# Bitirme_deneme.net
KiCad netlist of a schematic drawn in EAGLE
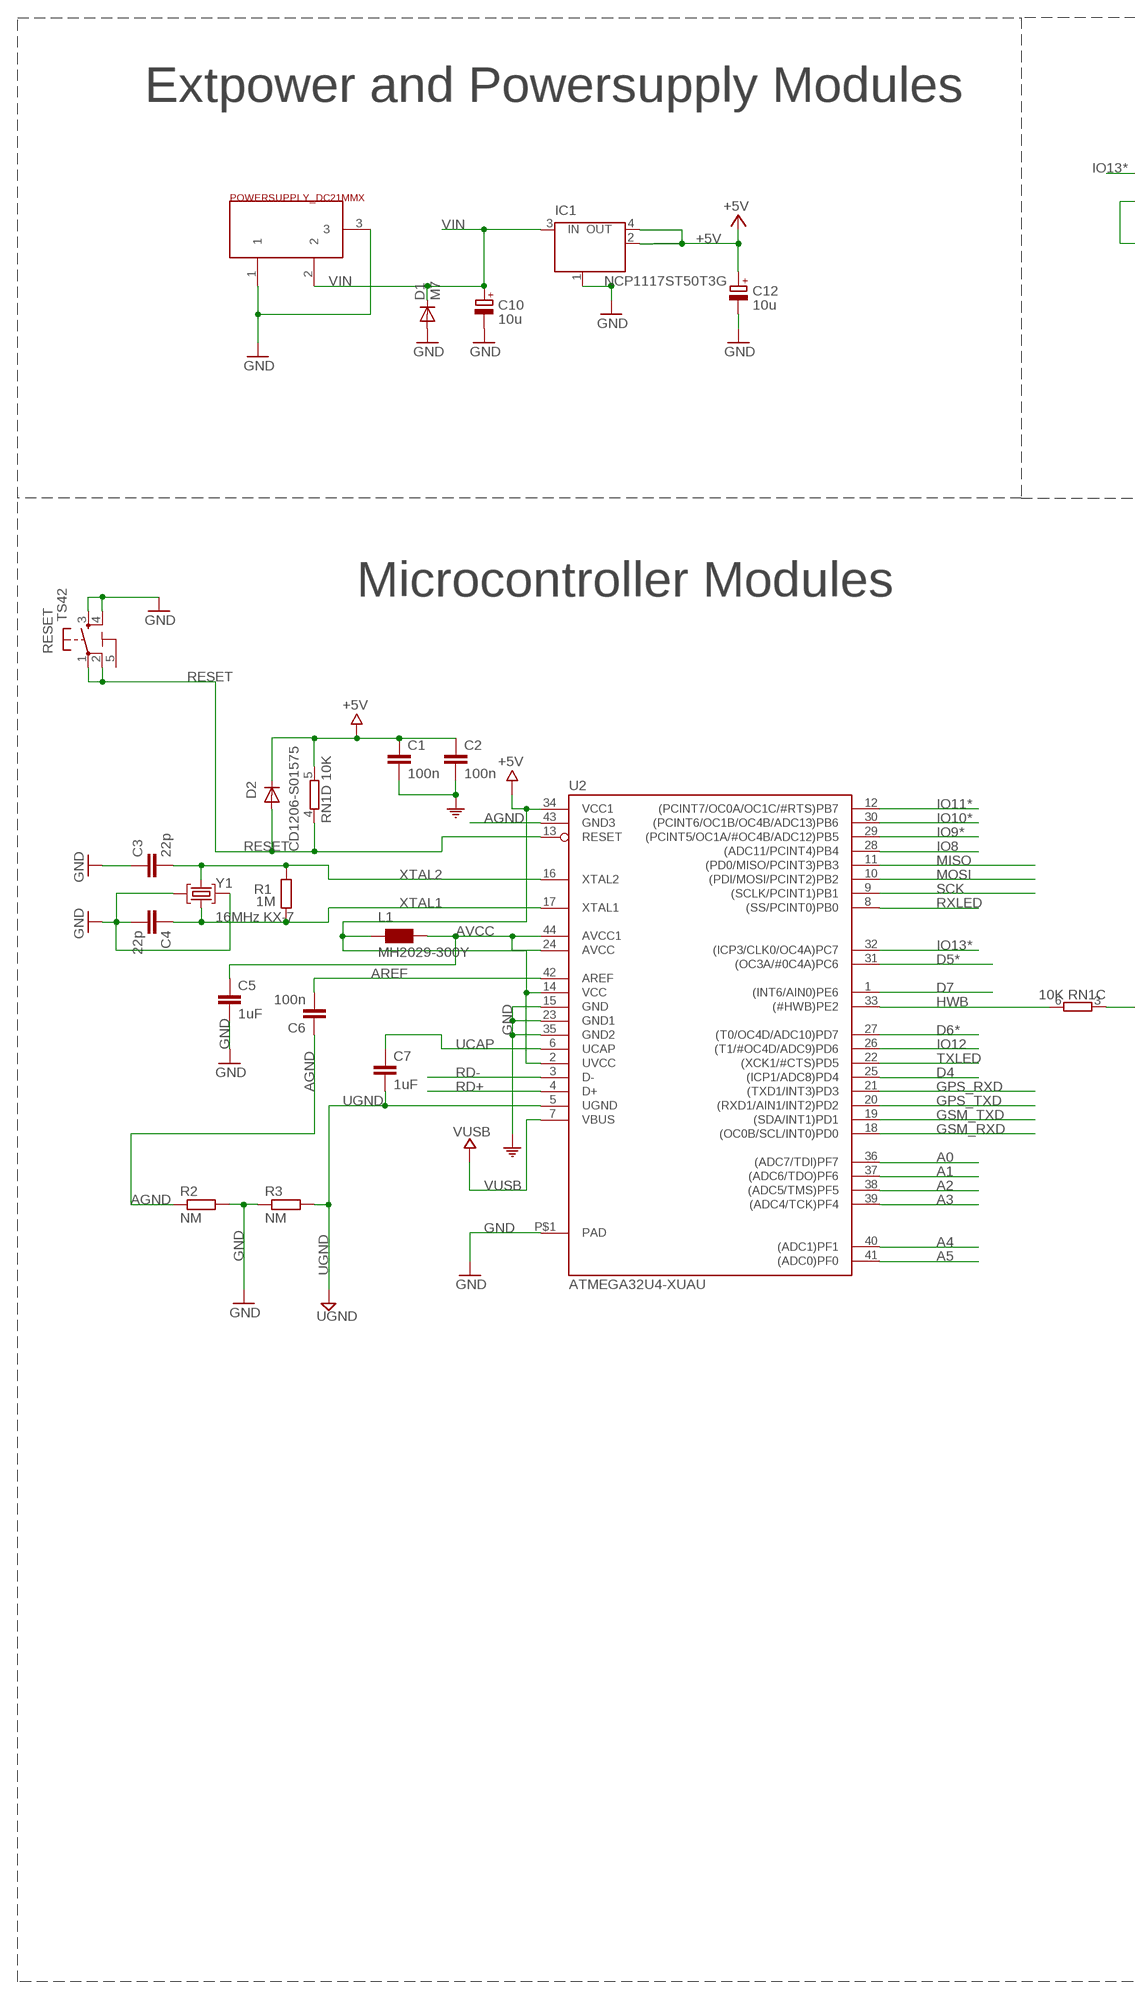
[diagram p0: schematic, sheet 1, part 1 of 2]
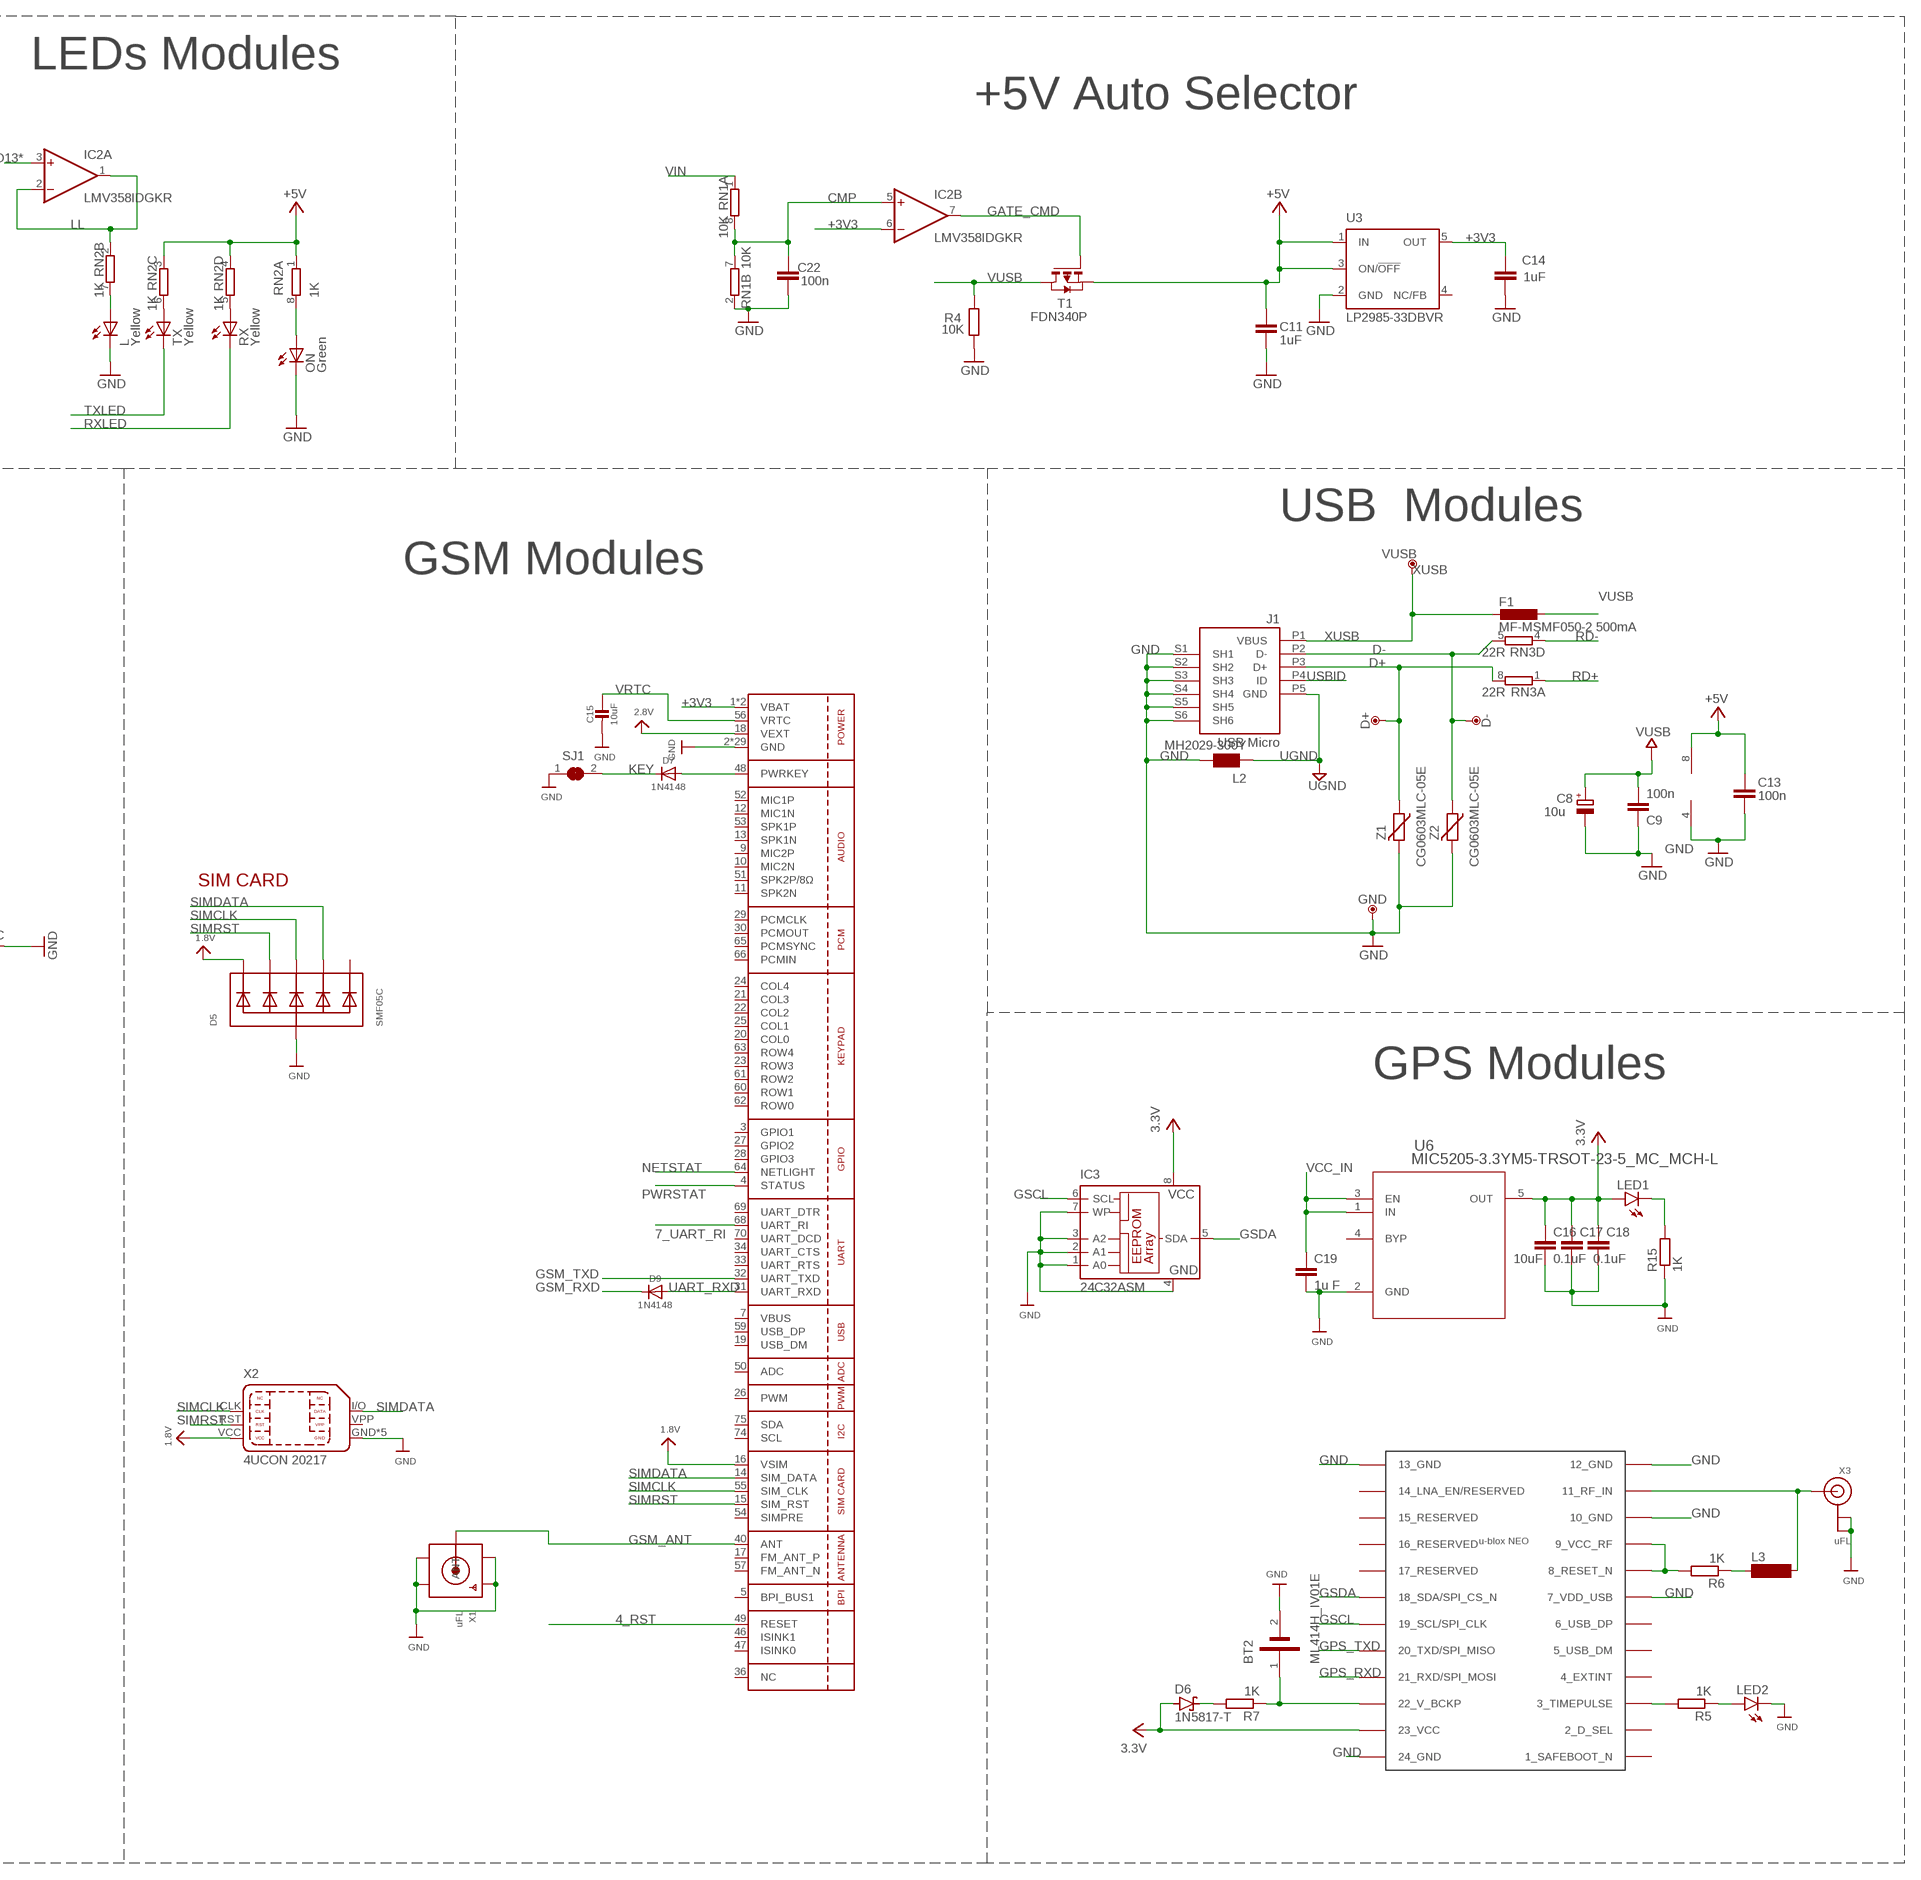
[diagram p1: schematic, sheet 1, part 2 of 2]

(export (version "E")
  (design (tool "Eeschema 10.0.6"))
  (components
    (comp (ref "BT2")
      (value "ML414H_IV01E")
      (footprint "eagle-import:SEIKO_ML414H_IV01E")
      (fields (field (name "MF") "Seiko Instruments") (field (name "MP") "ML414H IV01E"))
      (libsource (lib "eagle-import") (part "ML414H_IV01E"))
    )
    (comp (ref "C1")
      (value "100n")
      (footprint "eagle-import:C0603-ROUND")
      (libsource (lib "eagle-import") (part "C-EUC0603"))
    )
    (comp (ref "C2")
      (value "100n")
      (footprint "eagle-import:C0603-ROUND")
      (libsource (lib "eagle-import") (part "C-EUC0603"))
    )
    (comp (ref "C3")
      (value "22p")
      (footprint "eagle-import:C0603-ROUND")
      (libsource (lib "eagle-import") (part "C-EUC0603"))
    )
    (comp (ref "C4")
      (value "22p")
      (footprint "eagle-import:C0603-ROUND")
      (libsource (lib "eagle-import") (part "C-EUC0603"))
    )
    (comp (ref "C5")
      (value "1uF")
      (footprint "eagle-import:C0603-ROUND")
      (libsource (lib "eagle-import") (part "C-EUC0603"))
    )
    (comp (ref "C6")
      (value "100n")
      (footprint "eagle-import:C0603-ROUND")
      (libsource (lib "eagle-import") (part "C-EUC0603"))
    )
    (comp (ref "C7")
      (value "1uF")
      (footprint "eagle-import:C0603-ROUND")
      (libsource (lib "eagle-import") (part "C-EUC0603"))
    )
    (comp (ref "C8")
      (value "10u")
      (footprint "eagle-import:SMC_B")
      (libsource (lib "eagle-import") (part "CPOL-EUSMCB"))
    )
    (comp (ref "C9")
      (value "100n")
      (footprint "eagle-import:C0603-ROUND")
      (libsource (lib "eagle-import") (part "C-EUC0603"))
    )
    (comp (ref "C10")
      (value "10u")
      (footprint "eagle-import:SMC_B")
      (libsource (lib "eagle-import") (part "CPOL-EUSMCB"))
    )
    (comp (ref "C11")
      (value "1uF")
      (footprint "eagle-import:C0603-ROUND")
      (libsource (lib "eagle-import") (part "C-EUC0603"))
    )
    (comp (ref "C12")
      (value "10u")
      (footprint "eagle-import:SMC_B")
      (libsource (lib "eagle-import") (part "CPOL-EUSMCB"))
    )
    (comp (ref "C13")
      (value "100n")
      (footprint "eagle-import:C0603-ROUND")
      (libsource (lib "eagle-import") (part "C-EUC0603"))
    )
    (comp (ref "C14")
      (value "1uF")
      (footprint "eagle-import:C0603-ROUND")
      (libsource (lib "eagle-import") (part "C-EUC0603"))
    )
    (comp (ref "C15")
      (value "10uF")
      (footprint "eagle-import:_0805MP")
      (libsource (lib "eagle-import") (part "CAP_CERAMIC_0805MP"))
    )
    (comp (ref "C16")
      (value "10uF")
      (footprint "eagle-import:C0603K")
      (libsource (lib "eagle-import") (part "rcl_334_C-EUC0603K"))
    )
    (comp (ref "C17")
      (value "0.1uF")
      (footprint "eagle-import:C0603K")
      (libsource (lib "eagle-import") (part "rcl_334_C-EUC0603K"))
    )
    (comp (ref "C18")
      (value "0.1uF")
      (footprint "eagle-import:C0603K")
      (libsource (lib "eagle-import") (part "rcl_334_C-EUC0603K"))
    )
    (comp (ref "C19")
      (value "1u F")
      (footprint "eagle-import:C0603K")
      (libsource (lib "eagle-import") (part "rcl_334_C-EUC0603K"))
    )
    (comp (ref "C22")
      (value "100n")
      (footprint "eagle-import:C0603-ROUND")
      (libsource (lib "eagle-import") (part "C-EUC0603"))
    )
    (comp (ref "D+")
      (value "DNP")
      (footprint "eagle-import:TP-1.00MM")
      (libsource (lib "eagle-import") (part "TPTP-1.00MM"))
    )
    (comp (ref "D-")
      (value "DNP")
      (footprint "eagle-import:TP-1.00MM")
      (libsource (lib "eagle-import") (part "TPTP-1.00MM"))
    )
    (comp (ref "D1")
      (value "M7")
      (footprint "eagle-import:SMB")
      (libsource (lib "eagle-import") (part "DIODE-SMB"))
    )
    (comp (ref "D2")
      (value "CD1206-S01575")
      (footprint "eagle-import:MINIMELF")
      (libsource (lib "eagle-import") (part "DIODE-MINIMELF"))
    )
    (comp (ref "D5")
      (value "SMF05C")
      (footprint "eagle-import:SOT363")
      (libsource (lib "eagle-import") (part "TVSARRAY_5LANE"))
    )
    (comp (ref "D6")
      (value "1N5817-T")
      (footprint "eagle-import:DO41-7.6")
      (libsource (lib "eagle-import") (part "1N5817-T"))
    )
    (comp (ref "D7")
      (value "1N4148")
      (footprint "eagle-import:SOD-323")
      (libsource (lib "eagle-import") (part "DIODESOD-323"))
    )
    (comp (ref "D9")
      (value "1N4148")
      (footprint "eagle-import:SOD-323")
      (libsource (lib "eagle-import") (part "DIODESOD-323"))
    )
    (comp (ref "EXTPOWER")
      (value "POWERSUPPLY_DC21MMX")
      (footprint "eagle-import:POWERSUPPLY_DC-21MM")
      (libsource (lib "eagle-import") (part "POWERSUPPLY_DC21MMX"))
    )
    (comp (ref "F1")
      (value "MF-MSMF050-2 500mA")
      (footprint "eagle-import:L1812")
      (libsource (lib "eagle-import") (part "L-EUL1812"))
    )
    (comp (ref "GND")
      (value "DNP")
      (footprint "eagle-import:TP-1.00MM")
      (libsource (lib "eagle-import") (part "TPTP-1.00MM"))
    )
    (comp (ref "IC1")
      (value "NCP1117ST50T3G")
      (footprint "eagle-import:SOT223")
      (libsource (lib "eagle-import") (part "MC33269ST-3.3T3"))
    )
    (comp (ref "IC2")
      (value "LMV358IDGKR")
      (footprint "eagle-import:MSOP08")
      (libsource (lib "eagle-import") (part "LMV358?MMX"))
    )
    (comp (ref "IC3")
      (value "24C32ASM")
      (footprint "eagle-import:SO-08M")
      (fields (field (name "MPN") "IS24C32A-2GLI"))
      (libsource (lib "eagle-import") (part "24SMC32A"))
    )
    (comp (ref "J1")
      (value "USB Micro")
      (footprint "eagle-import:CON2_USB_MICRO_B_AT")
      (fields (field (name "MANUFACTURER") "FCI"))
      (libsource (lib "eagle-import") (part "USB-MICRO-LEGACY"))
    )
    (comp (ref "L")
      (value "Yellow")
      (footprint "eagle-import:CHIPLED_0805")
      (libsource (lib "eagle-import") (part "LEDCHIPLED_0805"))
    )
    (comp (ref "L1")
      (value "MH2029-300Y")
      (footprint "eagle-import:0805")
      (libsource (lib "eagle-import") (part "WE-CBF_0805"))
    )
    (comp (ref "L2")
      (value "MH2029-300Y")
      (footprint "eagle-import:0805")
      (libsource (lib "eagle-import") (part "WE-CBF_0805"))
    )
    (comp (ref "L3")
      (value "SM-1206")
      (footprint "eagle-import:SM-1206")
      (libsource (lib "eagle-import") (part "SM-1206"))
    )
    (comp (ref "LED1")
      (value "LEDCHIP-LED0603")
      (footprint "eagle-import:CHIP-LED0603")
      (libsource (lib "eagle-import") (part "led_259_LEDCHIP-LED0603"))
    )
    (comp (ref "LED2")
      (value "LEDCHIPLED_1206")
      (footprint "eagle-import:CHIPLED_1206")
      (libsource (lib "eagle-import") (part "led_259_LEDCHIPLED_1206"))
    )
    (comp (ref "ON")
      (value "Green")
      (footprint "eagle-import:CHIPLED_0805")
      (libsource (lib "eagle-import") (part "LEDCHIPLED_0805"))
    )
    (comp (ref "R1")
      (value "1M")
      (footprint "eagle-import:R0603-ROUND")
      (libsource (lib "eagle-import") (part "R-EU_R0603"))
    )
    (comp (ref "R2")
      (value "NM")
      (footprint "eagle-import:R0402")
      (libsource (lib "eagle-import") (part "R-EU_R0402"))
    )
    (comp (ref "R3")
      (value "NM")
      (footprint "eagle-import:R0402")
      (libsource (lib "eagle-import") (part "R-EU_R0402"))
    )
    (comp (ref "R4")
      (value "10K")
      (footprint "eagle-import:R0603-ROUND")
      (libsource (lib "eagle-import") (part "R-EU_R0603"))
    )
    (comp (ref "R5")
      (value "1K")
      (footprint "eagle-import:R0402")
      (libsource (lib "eagle-import") (part "R-EU_R0402"))
    )
    (comp (ref "R6")
      (value "1K")
      (footprint "eagle-import:R0402")
      (libsource (lib "eagle-import") (part "R-EU_R0402"))
    )
    (comp (ref "R7")
      (value "1K")
      (footprint "eagle-import:R0402")
      (libsource (lib "eagle-import") (part "R-EU_R0402"))
    )
    (comp (ref "R15")
      (value "1K")
      (footprint "eagle-import:R0402")
      (libsource (lib "eagle-import") (part "R-EU_R0402"))
    )
    (comp (ref "RESET")
      (value "TS42")
      (footprint "eagle-import:TS42")
      (libsource (lib "eagle-import") (part "TS42"))
    )
    (comp (ref "RN1")
      (value "10K")
      (footprint "eagle-import:CAY16")
      (libsource (lib "eagle-import") (part "4R-NCAY16"))
    )
    (comp (ref "RN2")
      (value "1K")
      (footprint "eagle-import:CAY16")
      (libsource (lib "eagle-import") (part "4R-NCAY16"))
    )
    (comp (ref "RN3")
      (value "22R")
      (footprint "eagle-import:CAY16")
      (libsource (lib "eagle-import") (part "4R-NCAY16"))
    )
    (comp (ref "RX")
      (value "Yellow")
      (footprint "eagle-import:CHIPLED_0805")
      (libsource (lib "eagle-import") (part "LEDCHIPLED_0805"))
    )
    (comp (ref "SJ1")
      (value "SOLDERJUMPER_CLOSED")
      (footprint "eagle-import:SOLDERJUMPER_CLOSEDWIRE")
      (libsource (lib "eagle-import") (part "SOLDERJUMPER_CLOSED"))
    )
    (comp (ref "T1")
      (value "FDN340P")
      (footprint "eagle-import:SOT-23")
      (libsource (lib "eagle-import") (part "PMOSSOT23"))
    )
    (comp (ref "TX")
      (value "Yellow")
      (footprint "eagle-import:CHIPLED_0805")
      (libsource (lib "eagle-import") (part "LEDCHIPLED_0805"))
    )
    (comp (ref "U$10")
      (value "NEO-M8")
      (footprint "eagle-import:NEO-M8")
      (libsource (lib "eagle-import") (part "NEO-M8"))
    )
    (comp (ref "U2")
      (value "ATMEGA32U4-XUAU")
      (footprint "eagle-import:TQFP44-PAD")
      (libsource (lib "eagle-import") (part "ATMEGA32U4-XUAU"))
    )
    (comp (ref "U3")
      (value "LP2985-33DBVR")
      (footprint "eagle-import:SOT23-DBV")
      (libsource (lib "eagle-import") (part "LP2985-XXDBVR33"))
    )
    (comp (ref "U4")
      (value "SIM800H/L")
      (footprint "eagle-import:SIM800L")
      (libsource (lib "eagle-import") (part "GSM_SIM800L"))
    )
    (comp (ref "U6")
      (value "MIC5205-3.3YM5-TRSOT-23-5_MC_MCH-L")
      (footprint "eagle-import:SOT-23-5_MC_MCH-L")
      (fields
        (field (name "MANUFACTURER_PART_NUMBER") "MIC5205-3.3YM5-TR")
        (field (name "COPYRIGHT") "Copyright (C) 2022 Ultra Librarian. All rights reserved.")
      )
      (libsource (lib "eagle-import") (part "MIC5205-3.3YM5-TRSOT-23-5_MC_MCH-L"))
    )
    (comp (ref "VUSB")
      (value "DNP")
      (footprint "eagle-import:TP-1.00MM")
      (libsource (lib "eagle-import") (part "TPTP-1.00MM"))
    )
    (comp (ref "X1")
      (value "uFL")
      (footprint "eagle-import:SMA_EDGELAUNCH_UFL")
      (libsource (lib "eagle-import") (part "SMACONNECTOR_EDGE_UFL"))
    )
    (comp (ref "X2")
      (value "4UCON 20217")
      (footprint "eagle-import:4UCONN_20217")
      (libsource (lib "eagle-import") (part "SIM_MICRO"))
    )
    (comp (ref "X3")
      (value "uFL")
      (footprint "eagle-import:U.FL")
      (libsource (lib "eagle-import") (part "ANTENNA_U.FL"))
    )
    (comp (ref "Y1")
      (value "16MHz KX-7")
      (footprint "eagle-import:CRYSTAL-3.2-2.5")
      (libsource (lib "eagle-import") (part "CRYSTAL-3.2-2.5"))
    )
    (comp (ref "Z1")
      (value "CG0603MLC-05E")
      (footprint "eagle-import:CT_CN0603")
      (libsource (lib "eagle-import") (part "VARISTORCN0603"))
    )
    (comp (ref "Z2")
      (value "CG0603MLC-05E")
      (footprint "eagle-import:CT_CN0603")
      (libsource (lib "eagle-import") (part "VARISTORCN0603"))
    )
  )
  (nets
    (net (code "1") (name "+5V") (class "Default")
      (node (ref "C1") (pin "1") (pinfunction "1_1") (pintype "passive"))
      (node (ref "C11") (pin "2") (pinfunction "2_2") (pintype "passive"))
      (node (ref "C12") (pin "+") (pinfunction "+_+") (pintype "passive"))
      (node (ref "C13") (pin "1") (pinfunction "1_1") (pintype "passive"))
      (node (ref "C2") (pin "1") (pinfunction "1_1") (pintype "passive"))
      (node (ref "D2") (pin "C") (pinfunction "C_C") (pintype "passive"))
      (node (ref "IC1") (pin "2") (pinfunction "OUT_2") (pintype "passive"))
      (node (ref "IC1") (pin "4") (pinfunction "OUT_4") (pintype "passive"))
      (node (ref "IC2") (pin "8") (pinfunction "V+_8") (pintype "power_in"))
      (node (ref "L1") (pin "1") (pinfunction "1_1") (pintype "passive"))
      (node (ref "RN1") (pin "5") (pinfunction "2_5") (pintype "passive"))
      (node (ref "RN2") (pin "1") (pinfunction "1_1") (pintype "passive"))
      (node (ref "RN2") (pin "3") (pinfunction "1_3") (pintype "passive"))
      (node (ref "RN2") (pin "4") (pinfunction "1_4") (pintype "passive"))
      (node (ref "T1") (pin "2") (pinfunction "S_2") (pintype "passive"))
      (node (ref "U2") (pin "14") (pinfunction "VCC_14") (pintype "power_in"))
      (node (ref "U2") (pin "2") (pinfunction "UVCC_2") (pintype "power_in"))
      (node (ref "U2") (pin "34") (pinfunction "VCC1_34") (pintype "power_in"))
      (node (ref "U3") (pin "1") (pinfunction "IN_1") (pintype "input"))
      (node (ref "U3") (pin "3") (pinfunction "ON/~{OFF}_3") (pintype "input"))
    )
    (net (code "2") (name "/+3V3") (class "Default")
      (node (ref "C14") (pin "2") (pinfunction "2_2") (pintype "passive"))
      (node (ref "IC2") (pin "6") (pinfunction "-IN_6") (pintype "input"))
      (node (ref "U3") (pin "5") (pinfunction "OUT_5") (pintype "passive"))
      (node (ref "U4") (pin "1") (pinfunction "VBAT_1") (pintype "power_in"))
      (node (ref "U4") (pin "42") (pinfunction "VBAT_42") (pintype "power_in"))
    )
    (net (code "3") (name "/4_RST") (class "Default")
      (node (ref "U4") (pin "49") (pinfunction "RESET_49") (pintype "input"))
    )
    (net (code "4") (name "/5-GND") (class "Default")
      (node (ref "RESET") (pin "5") (pinfunction "5-GND_5") (pintype "power_in"))
    )
    (net (code "5") (name "/7_UART_RI") (class "Default")
      (node (ref "U4") (pin "68") (pinfunction "UART_RI_68") (pintype "output"))
    )
    (net (code "6") (name "/A0") (class "Default")
      (node (ref "U2") (pin "36") (pinfunction "(ADC7/TDI)PF7_36") (pintype "bidirectional"))
    )
    (net (code "7") (name "/A1") (class "Default")
      (node (ref "U2") (pin "37") (pinfunction "(ADC6/TDO)PF6_37") (pintype "bidirectional"))
    )
    (net (code "8") (name "/A2") (class "Default")
      (node (ref "U2") (pin "38") (pinfunction "(ADC5/TMS)PF5_38") (pintype "bidirectional"))
    )
    (net (code "9") (name "/A3") (class "Default")
      (node (ref "U2") (pin "39") (pinfunction "(ADC4/TCK)PF4_39") (pintype "bidirectional"))
    )
    (net (code "10") (name "/A4") (class "Default")
      (node (ref "U2") (pin "40") (pinfunction "(ADC1)PF1_40") (pintype "bidirectional"))
    )
    (net (code "11") (name "/A5") (class "Default")
      (node (ref "U2") (pin "41") (pinfunction "(ADC0)PF0_41") (pintype "bidirectional"))
    )
    (net (code "12") (name "/AGND") (class "Default")
      (node (ref "C6") (pin "1") (pinfunction "1_1") (pintype "passive"))
      (node (ref "R2") (pin "1") (pinfunction "1_1") (pintype "passive"))
      (node (ref "U2") (pin "43") (pinfunction "GND3_43") (pintype "power_in"))
    )
    (net (code "13") (name "/AREF") (class "Default")
      (node (ref "C6") (pin "2") (pinfunction "2_2") (pintype "passive"))
      (node (ref "U2") (pin "42") (pinfunction "AREF_42") (pintype "power_in"))
    )
    (net (code "14") (name "/AVCC") (class "Default")
      (node (ref "C5") (pin "1") (pinfunction "1_1") (pintype "passive"))
      (node (ref "L1") (pin "2") (pinfunction "2_2") (pintype "passive"))
      (node (ref "U2") (pin "24") (pinfunction "AVCC_24") (pintype "power_in"))
      (node (ref "U2") (pin "44") (pinfunction "AVCC1_44") (pintype "power_in"))
    )
    (net (code "15") (name "/CMP") (class "Default")
      (node (ref "C22") (pin "2") (pinfunction "2_2") (pintype "passive"))
      (node (ref "IC2") (pin "5") (pinfunction "+IN_5") (pintype "input"))
      (node (ref "RN1") (pin "7") (pinfunction "2_7") (pintype "passive"))
      (node (ref "RN1") (pin "8") (pinfunction "2_8") (pintype "passive"))
    )
    (net (code "16") (name "/D+") (class "Default")
      (node (ref "D+") (pin "X") (pinfunction "P$1_X") (pintype "passive"))
      (node (ref "J1") (pin "P3") (pinfunction "D+_P3") (pintype "bidirectional"))
      (node (ref "RN3") (pin "8") (pinfunction "2_8") (pintype "passive"))
      (node (ref "Z1") (pin "1") (pinfunction "1_1") (pintype "passive"))
    )
    (net (code "17") (name "/D-") (class "Default")
      (node (ref "D-") (pin "X") (pinfunction "P$1_X") (pintype "passive"))
      (node (ref "J1") (pin "P2") (pinfunction "D-_P2") (pintype "bidirectional"))
      (node (ref "RN3") (pin "5") (pinfunction "2_5") (pintype "passive"))
      (node (ref "Z2") (pin "1") (pinfunction "1_1") (pintype "passive"))
    )
    (net (code "18") (name "/D4") (class "Default")
      (node (ref "U2") (pin "25") (pinfunction "(ICP1/ADC8)PD4_25") (pintype "bidirectional"))
    )
    (net (code "19") (name "/D5*") (class "Default")
      (node (ref "U2") (pin "31") (pinfunction "(OC3A/#0C4A)PC6_31") (pintype "bidirectional"))
    )
    (net (code "20") (name "/D6*") (class "Default")
      (node (ref "U2") (pin "27") (pinfunction "(T0/OC4D/ADC10)PD7_27") (pintype "bidirectional"))
    )
    (net (code "21") (name "/D7") (class "Default")
      (node (ref "U2") (pin "1") (pinfunction "(INT6/AIN0)PE6_1") (pintype "bidirectional"))
    )
    (net (code "22") (name "/GATE_CMD") (class "Default")
      (node (ref "IC2") (pin "7") (pinfunction "OUT_7") (pintype "output"))
      (node (ref "T1") (pin "3") (pinfunction "G_3") (pintype "passive"))
    )
    (net (code "23") (name "/GPS_RXD") (class "Default")
      (node (ref "U$10") (pin "21") (pinfunction "21_RXD/SPI_MOSI_21") (pintype "bidirectional"))
      (node (ref "U2") (pin "21") (pinfunction "(TXD1/INT3)PD3_21") (pintype "bidirectional"))
    )
    (net (code "24") (name "/GPS_TXD") (class "Default")
      (node (ref "U$10") (pin "20") (pinfunction "20_TXD/SPI_MISO_20") (pintype "bidirectional"))
      (node (ref "U2") (pin "20") (pinfunction "(RXD1/AIN1/INT2)PD2_20") (pintype "bidirectional"))
    )
    (net (code "25") (name "/GSCL") (class "Default")
      (node (ref "IC3") (pin "6") (pinfunction "SCL_6") (pintype "input"))
      (node (ref "U$10") (pin "19") (pinfunction "19_SCL/SPI_CLK_19") (pintype "bidirectional"))
    )
    (net (code "26") (name "/GSDA") (class "Default")
      (node (ref "IC3") (pin "5") (pinfunction "SDA_5") (pintype "bidirectional"))
      (node (ref "U$10") (pin "18") (pinfunction "18_SDA/SPI_CS_N_18") (pintype "bidirectional"))
    )
    (net (code "27") (name "/GSM_ANT") (class "Default")
      (node (ref "U4") (pin "40") (pinfunction "ANT_40") (pintype "bidirectional"))
      (node (ref "X1") (pin "P") (pinfunction "ANT_P") (pintype "bidirectional"))
    )
    (net (code "28") (name "/GSM_RXD") (class "Default")
      (node (ref "D9") (pin "C") (pinfunction "C_C") (pintype "passive"))
      (node (ref "U2") (pin "18") (pinfunction "(OC0B/SCL/INT0)PD0_18") (pintype "bidirectional"))
    )
    (net (code "29") (name "/GSM_TXD") (class "Default")
      (node (ref "U2") (pin "19") (pinfunction "(SDA/INT1)PD1_19") (pintype "bidirectional"))
      (node (ref "U4") (pin "32") (pinfunction "UART_TXD_32") (pintype "output"))
    )
    (net (code "30") (name "/HWB") (class "Default")
      (node (ref "RN1") (pin "6") (pinfunction "2_6") (pintype "passive"))
      (node (ref "U2") (pin "33") (pinfunction "(#HWB)PE2_33") (pintype "bidirectional"))
    )
    (net (code "31") (name "/IO8") (class "Default")
      (node (ref "U2") (pin "28") (pinfunction "(ADC11/PCINT4)PB4_28") (pintype "bidirectional"))
    )
    (net (code "32") (name "/IO9*") (class "Default")
      (node (ref "U2") (pin "29") (pinfunction "(PCINT5/OC1A/#OC4B/ADC12)PB5_29") (pintype "bidirectional"))
    )
    (net (code "33") (name "/IO10*") (class "Default")
      (node (ref "U2") (pin "30") (pinfunction "(PCINT6/OC1B/OC4B/ADC13)PB6_30") (pintype "bidirectional"))
    )
    (net (code "34") (name "/IO11*") (class "Default")
      (node (ref "U2") (pin "12") (pinfunction "(PCINT7/OC0A/OC1C/#RTS)PB7_12") (pintype "bidirectional"))
    )
    (net (code "35") (name "/IO12") (class "Default")
      (node (ref "U2") (pin "26") (pinfunction "(T1/#OC4D/ADC9)PD6_26") (pintype "bidirectional"))
    )
    (net (code "36") (name "/IO13*") (class "Default")
      (node (ref "IC2") (pin "3") (pinfunction "+IN_3") (pintype "input"))
      (node (ref "U2") (pin "32") (pinfunction "(ICP3/CLK0/OC4A)PC7_32") (pintype "bidirectional"))
    )
    (net (code "37") (name "/KEY") (class "Default")
      (node (ref "D7") (pin "C") (pinfunction "C_C") (pintype "passive"))
      (node (ref "SJ1") (pin "2") (pinfunction "2_2") (pintype "passive"))
    )
    (net (code "38") (name "/LL") (class "Default")
      (node (ref "IC2") (pin "1") (pinfunction "OUT_1") (pintype "output"))
      (node (ref "IC2") (pin "2") (pinfunction "-IN_2") (pintype "input"))
      (node (ref "RN2") (pin "2") (pinfunction "1_2") (pintype "passive"))
    )
    (net (code "39") (name "/MISO") (class "Default")
      (node (ref "U2") (pin "11") (pinfunction "(PD0/MISO/PCINT3)PB3_11") (pintype "bidirectional"))
    )
    (net (code "40") (name "/MOSI") (class "Default")
      (node (ref "U2") (pin "10") (pinfunction "(PDI/MOSI/PCINT2)PB2_10") (pintype "bidirectional"))
    )
    (net (code "41") (name "/NETSTAT") (class "Default")
      (node (ref "U4") (pin "64") (pinfunction "NETLIGHT_64") (pintype "output"))
    )
    (net (code "42") (name "/PWRSTAT") (class "Default")
      (node (ref "U4") (pin "4") (pinfunction "STATUS_4") (pintype "output"))
    )
    (net (code "43") (name "/RD+") (class "Default")
      (node (ref "RN3") (pin "1") (pinfunction "1_1") (pintype "passive"))
      (node (ref "U2") (pin "4") (pinfunction "D+_4") (pintype "bidirectional"))
    )
    (net (code "44") (name "/RD-") (class "Default")
      (node (ref "RN3") (pin "4") (pinfunction "1_4") (pintype "passive"))
      (node (ref "U2") (pin "3") (pinfunction "D-_3") (pintype "bidirectional"))
    )
    (net (code "45") (name "/RESET") (class "Default")
      (node (ref "D2") (pin "A") (pinfunction "A_A") (pintype "passive"))
      (node (ref "RESET") (pin "1") (pinfunction "1_1") (pintype "passive"))
      (node (ref "RESET") (pin "2") (pinfunction "2_2") (pintype "passive"))
      (node (ref "RN1") (pin "4") (pinfunction "1_4") (pintype "passive"))
      (node (ref "U2") (pin "13") (pinfunction "RESET_13") (pintype "input"))
    )
    (net (code "46") (name "/RXLED") (class "Default")
      (node (ref "RX") (pin "C") (pinfunction "C_C") (pintype "passive"))
      (node (ref "U2") (pin "8") (pinfunction "(SS/PCINT0)PB0_8") (pintype "bidirectional"))
    )
    (net (code "47") (name "/SCK") (class "Default")
      (node (ref "U2") (pin "9") (pinfunction "(SCLK/PCINT1)PB1_9") (pintype "bidirectional"))
    )
    (net (code "48") (name "/SIMCLK") (class "Default")
      (node (ref "D5") (pin "4") (pinfunction "C3_4") (pintype "passive"))
      (node (ref "U4") (pin "55") (pinfunction "SIM_CLK_55") (pintype "output"))
      (node (ref "X2") (pin "CLK") (pinfunction "CLK_CLK") (pintype "passive"))
    )
    (net (code "49") (name "/SIMDATA") (class "Default")
      (node (ref "D5") (pin "5") (pinfunction "C4_5") (pintype "passive"))
      (node (ref "U4") (pin "14") (pinfunction "SIM_DATA_14") (pintype "bidirectional"))
      (node (ref "X2") (pin "I/O") (pinfunction "DATA_I/O") (pintype "passive"))
    )
    (net (code "50") (name "/SIMRST") (class "Default")
      (node (ref "D5") (pin "3") (pinfunction "C2_3") (pintype "passive"))
      (node (ref "U4") (pin "15") (pinfunction "SIM_RST_15") (pintype "output"))
      (node (ref "X2") (pin "RST") (pinfunction "RST_RST") (pintype "passive"))
    )
    (net (code "51") (name "/TXLED") (class "Default")
      (node (ref "TX") (pin "C") (pinfunction "C_C") (pintype "passive"))
      (node (ref "U2") (pin "22") (pinfunction "(XCK1/#CTS)PD5_22") (pintype "bidirectional"))
    )
    (net (code "52") (name "/UART_RXD") (class "Default")
      (node (ref "D9") (pin "A") (pinfunction "A_A") (pintype "passive"))
      (node (ref "U4") (pin "31") (pinfunction "UART_RXD_31") (pintype "input"))
    )
    (net (code "53") (name "/UCAP") (class "Default")
      (node (ref "C7") (pin "1") (pinfunction "1_1") (pintype "passive"))
      (node (ref "U2") (pin "6") (pinfunction "UCAP_6") (pintype "passive"))
    )
    (net (code "54") (name "/USBID") (class "Default")
      (node (ref "J1") (pin "P4") (pinfunction "ID_P4") (pintype "bidirectional"))
    )
    (net (code "55") (name "/VBUS") (class "Default")
      (node (ref "U4") (pin "7") (pinfunction "VBUS_7") (pintype "power_in"))
    )
    (net (code "56") (name "/VCC_IN") (class "Default")
      (node (ref "C19") (pin "1") (pinfunction "1_1") (pintype "passive"))
      (node (ref "U6") (pin "1") (pinfunction "IN_1") (pintype "input"))
      (node (ref "U6") (pin "3") (pinfunction "EN_3") (pintype "input"))
    )
    (net (code "57") (name "/VIN") (class "Default")
      (node (ref "C10") (pin "+") (pinfunction "+_+") (pintype "passive"))
      (node (ref "D1") (pin "C") (pinfunction "C_C") (pintype "passive"))
      (node (ref "EXTPOWER") (pin "2") (pinfunction "2_2") (pintype "power_in"))
      (node (ref "IC1") (pin "3") (pinfunction "IN_3") (pintype "input"))
      (node (ref "RN1") (pin "1") (pinfunction "1_1") (pintype "passive"))
    )
    (net (code "58") (name "/VRTC") (class "Default")
      (node (ref "C15") (pin "1") (pinfunction "1_1") (pintype "passive"))
      (node (ref "U4") (pin "56") (pinfunction "VRTC_56") (pintype "power_in"))
    )
    (net (code "59") (name "/XTAL1") (class "Default")
      (node (ref "C4") (pin "1") (pinfunction "1_1") (pintype "passive"))
      (node (ref "R1") (pin "1") (pinfunction "1_1") (pintype "passive"))
      (node (ref "U2") (pin "17") (pinfunction "XTAL1_17") (pintype "bidirectional"))
      (node (ref "Y1") (pin "1") (pinfunction "C1_1") (pintype "passive"))
    )
    (net (code "60") (name "/XTAL2") (class "Default")
      (node (ref "C3") (pin "2") (pinfunction "2_2") (pintype "passive"))
      (node (ref "R1") (pin "2") (pinfunction "2_2") (pintype "passive"))
      (node (ref "U2") (pin "16") (pinfunction "XTAL2_16") (pintype "bidirectional"))
      (node (ref "Y1") (pin "3") (pinfunction "C2_3") (pintype "passive"))
    )
    (net (code "61") (name "/XUSB") (class "Default")
      (node (ref "F1") (pin "2") (pinfunction "2_2") (pintype "passive"))
      (node (ref "J1") (pin "P1") (pinfunction "VBUS_P1") (pintype "power_in"))
      (node (ref "VUSB") (pin "X") (pinfunction "P$1_X") (pintype "passive"))
    )
    (net (code "62") (name "1.8V") (class "Default")
      (node (ref "D5") (pin "1") (pinfunction "C1_1") (pintype "passive"))
      (node (ref "U4") (pin "16") (pinfunction "VSIM_16") (pintype "power_in"))
      (node (ref "X2") (pin "VCC") (pinfunction "VCC_VCC") (pintype "passive"))
    )
    (net (code "63") (name "2.8V") (class "Default")
      (node (ref "U4") (pin "18") (pinfunction "VEXT_18") (pintype "power_in"))
    )
    (net (code "64") (name "3.3V") (class "Default")
      (node (ref "C16") (pin "1") (pinfunction "1_1") (pintype "passive"))
      (node (ref "C17") (pin "1") (pinfunction "1_1") (pintype "passive"))
      (node (ref "C18") (pin "1") (pinfunction "1_1") (pintype "passive"))
      (node (ref "D6") (pin "A") (pinfunction "A_A") (pintype "passive"))
      (node (ref "IC3") (pin "8") (pinfunction "VCC_8") (pintype "power_in"))
      (node (ref "LED1") (pin "A") (pinfunction "A_A") (pintype "passive"))
      (node (ref "U$10") (pin "23") (pinfunction "23_VCC_23") (pintype "bidirectional"))
      (node (ref "U6") (pin "5") (pinfunction "OUT_5") (pintype "output"))
    )
    (net (code "65") (name "COM") (class "Default")
      (node (ref "BT2") (pin "2") (pinfunction "NEG_2") (pintype "passive"))
      (node (ref "C1") (pin "2") (pinfunction "2_2") (pintype "passive"))
      (node (ref "C10") (pin "-") (pinfunction "-_-") (pintype "passive"))
      (node (ref "C11") (pin "1") (pinfunction "1_1") (pintype "passive"))
      (node (ref "C12") (pin "-") (pinfunction "-_-") (pintype "passive"))
      (node (ref "C13") (pin "2") (pinfunction "2_2") (pintype "passive"))
      (node (ref "C14") (pin "1") (pinfunction "1_1") (pintype "passive"))
      (node (ref "C15") (pin "2") (pinfunction "2_2") (pintype "passive"))
      (node (ref "C16") (pin "2") (pinfunction "2_2") (pintype "passive"))
      (node (ref "C17") (pin "2") (pinfunction "2_2") (pintype "passive"))
      (node (ref "C18") (pin "2") (pinfunction "2_2") (pintype "passive"))
      (node (ref "C19") (pin "2") (pinfunction "2_2") (pintype "passive"))
      (node (ref "C2") (pin "2") (pinfunction "2_2") (pintype "passive"))
      (node (ref "C22") (pin "1") (pinfunction "1_1") (pintype "passive"))
      (node (ref "C3") (pin "1") (pinfunction "1_1") (pintype "passive"))
      (node (ref "C4") (pin "2") (pinfunction "2_2") (pintype "passive"))
      (node (ref "C5") (pin "2") (pinfunction "2_2") (pintype "passive"))
      (node (ref "C8") (pin "-") (pinfunction "-_-") (pintype "passive"))
      (node (ref "C9") (pin "1") (pinfunction "1_1") (pintype "passive"))
      (node (ref "D1") (pin "A") (pinfunction "A_A") (pintype "passive"))
      (node (ref "D5") (pin "2") (pinfunction "A_2") (pintype "passive"))
      (node (ref "EXTPOWER") (pin "1") (pinfunction "1_1") (pintype "power_in"))
      (node (ref "EXTPOWER") (pin "3") (pinfunction "3_3") (pintype "power_in"))
      (node (ref "GND") (pin "X") (pinfunction "P$1_X") (pintype "passive"))
      (node (ref "IC1") (pin "1") (pinfunction "GND/ADJ_1") (pintype "input"))
      (node (ref "IC2") (pin "4") (pinfunction "V-_4") (pintype "power_in"))
      (node (ref "IC3") (pin "1") (pinfunction "A0_1") (pintype "input"))
      (node (ref "IC3") (pin "2") (pinfunction "A1_2") (pintype "input"))
      (node (ref "IC3") (pin "3") (pinfunction "A2_3") (pintype "input"))
      (node (ref "IC3") (pin "4") (pinfunction "GND_4") (pintype "power_in"))
      (node (ref "IC3") (pin "7") (pinfunction "WP_7") (pintype "input"))
      (node (ref "J1") (pin "S1") (pinfunction "SH1_S1") (pintype "passive"))
      (node (ref "J1") (pin "S2") (pinfunction "SH2_S2") (pintype "passive"))
      (node (ref "J1") (pin "S3") (pinfunction "SH3_S3") (pintype "passive"))
      (node (ref "J1") (pin "S4") (pinfunction "SH4_S4") (pintype "passive"))
      (node (ref "J1") (pin "S5") (pinfunction "SH5_S5") (pintype "passive"))
      (node (ref "J1") (pin "S6") (pinfunction "SH6_S6") (pintype "passive"))
      (node (ref "L") (pin "C") (pinfunction "C_C") (pintype "passive"))
      (node (ref "L2") (pin "2") (pinfunction "2_2") (pintype "passive"))
      (node (ref "LED2") (pin "C") (pinfunction "C_C") (pintype "passive"))
      (node (ref "ON") (pin "C") (pinfunction "C_C") (pintype "passive"))
      (node (ref "R15") (pin "1") (pinfunction "1_1") (pintype "passive"))
      (node (ref "R2") (pin "2") (pinfunction "2_2") (pintype "passive"))
      (node (ref "R3") (pin "1") (pinfunction "1_1") (pintype "passive"))
      (node (ref "R4") (pin "1") (pinfunction "1_1") (pintype "passive"))
      (node (ref "RESET") (pin "3") (pinfunction "3_3") (pintype "passive"))
      (node (ref "RESET") (pin "4") (pinfunction "4_4") (pintype "passive"))
      (node (ref "RN1") (pin "2") (pinfunction "1_2") (pintype "passive"))
      (node (ref "RN1") (pin "3") (pinfunction "1_3") (pintype "passive"))
      (node (ref "SJ1") (pin "1") (pinfunction "1_1") (pintype "passive"))
      (node (ref "U$10") (pin "10") (pinfunction "10_GND_10") (pintype "bidirectional"))
      (node (ref "U$10") (pin "12") (pinfunction "12_GND_12") (pintype "bidirectional"))
      (node (ref "U$10") (pin "13") (pinfunction "13_GND_13") (pintype "bidirectional"))
      (node (ref "U$10") (pin "24") (pinfunction "24_GND_24") (pintype "bidirectional"))
      (node (ref "U$10") (pin "7") (pinfunction "7_VDD_USB_7") (pintype "bidirectional"))
      (node (ref "U2") (pin "15") (pinfunction "GND_15") (pintype "power_in"))
      (node (ref "U2") (pin "23") (pinfunction "GND1_23") (pintype "power_in"))
      (node (ref "U2") (pin "35") (pinfunction "GND2_35") (pintype "power_in"))
      (node (ref "U2") (pin "P$1") (pinfunction "PAD_P$1") (pintype "power_in"))
      (node (ref "U3") (pin "2") (pinfunction "GND_2") (pintype "power_in"))
      (node (ref "U4") (pin "2") (pinfunction "GND_2") (pintype "power_in"))
      (node (ref "U4") (pin "35") (pinfunction "GND_35") (pintype "power_in"))
      (node (ref "U4") (pin "37") (pinfunction "GND_37") (pintype "power_in"))
      (node (ref "U4") (pin "38") (pinfunction "GND_38") (pintype "power_in"))
      (node (ref "U4") (pin "39") (pinfunction "GND_39") (pintype "power_in"))
      (node (ref "U4") (pin "41") (pinfunction "GND_41") (pintype "power_in"))
      (node (ref "U4") (pin "43") (pinfunction "GND_43") (pintype "power_in"))
      (node (ref "U4") (pin "44") (pinfunction "GND_44") (pintype "power_in"))
      (node (ref "U4") (pin "45") (pinfunction "GND_45") (pintype "power_in"))
      (node (ref "U4") (pin "58") (pinfunction "GND_58") (pintype "power_in"))
      (node (ref "U4") (pin "6") (pinfunction "GND_6") (pintype "power_in"))
      (node (ref "U4") (pin "67") (pinfunction "GND_67") (pintype "power_in"))
      (node (ref "U4") (pin "71") (pinfunction "GND_71") (pintype "power_in"))
      (node (ref "U4") (pin "72") (pinfunction "GND_72") (pintype "power_in"))
      (node (ref "U4") (pin "73") (pinfunction "GND_73") (pintype "power_in"))
      (node (ref "U4") (pin "76") (pinfunction "GND_76") (pintype "power_in"))
      (node (ref "U4") (pin "77") (pinfunction "GND_77") (pintype "power_in"))
      (node (ref "U4") (pin "78") (pinfunction "GND_78") (pintype "power_in"))
      (node (ref "U4") (pin "79") (pinfunction "GND_79") (pintype "power_in"))
      (node (ref "U4") (pin "8") (pinfunction "GND_8") (pintype "power_in"))
      (node (ref "U4") (pin "80") (pinfunction "GND_80") (pintype "power_in"))
      (node (ref "U4") (pin "81") (pinfunction "GND_81") (pintype "power_in"))
      (node (ref "U4") (pin "82") (pinfunction "GND_82") (pintype "power_in"))
      (node (ref "U4") (pin "83") (pinfunction "GND_83") (pintype "power_in"))
      (node (ref "U4") (pin "84") (pinfunction "GND_84") (pintype "power_in"))
      (node (ref "U4") (pin "85") (pinfunction "GND_85") (pintype "power_in"))
      (node (ref "U4") (pin "86") (pinfunction "GND_86") (pintype "power_in"))
      (node (ref "U4") (pin "87") (pinfunction "GND_87") (pintype "power_in"))
      (node (ref "U4") (pin "88") (pinfunction "GND_88") (pintype "power_in"))
      (node (ref "U6") (pin "2") (pinfunction "GND_2") (pintype "power_in"))
      (node (ref "X1") (pin "GND@1") (pinfunction "GND1_GND@1") (pintype "power_in"))
      (node (ref "X1") (pin "GND@2") (pinfunction "GND2_GND@2") (pintype "power_in"))
      (node (ref "X1") (pin "GND@3") (pinfunction "GND3_GND@3") (pintype "power_in"))
      (node (ref "X1") (pin "GND@4") (pinfunction "GND4_GND@4") (pintype "power_in"))
      (node (ref "X2") (pin "GND") (pinfunction "GND_GND") (pintype "passive"))
      (node (ref "X2") (pin "GND@1") (pinfunction "GND_GND@1") (pintype "passive"))
      (node (ref "X2") (pin "GND@2") (pinfunction "GND_GND@2") (pintype "passive"))
      (node (ref "X2") (pin "GND@3") (pinfunction "GND_GND@3") (pintype "passive"))
      (node (ref "X2") (pin "GND@4") (pinfunction "GND_GND@4") (pintype "passive"))
      (node (ref "X3") (pin "1") (pinfunction "GND_1") (pintype "passive"))
      (node (ref "X3") (pin "2") (pinfunction "GND_2") (pintype "passive"))
      (node (ref "Y1") (pin "2") (pinfunction "GND_2") (pintype "passive"))
      (node (ref "Y1") (pin "4") (pinfunction "GND_4") (pintype "passive"))
      (node (ref "Z1") (pin "2") (pinfunction "2_2") (pintype "passive"))
      (node (ref "Z2") (pin "2") (pinfunction "2_2") (pintype "passive"))
    )
    (net (code "66") (name "Net-(BT2-POS)") (class "Default")
      (node (ref "BT2") (pin "1") (pinfunction "POS_1") (pintype "passive"))
      (node (ref "R7") (pin "1") (pinfunction "1_1") (pintype "passive"))
      (node (ref "U$10") (pin "22") (pinfunction "22_V_BCKP_22") (pintype "bidirectional"))
    )
    (net (code "67") (name "Net-(D6-PadC)") (class "Default")
      (node (ref "D6") (pin "C") (pinfunction "C_C") (pintype "passive"))
      (node (ref "R7") (pin "2") (pinfunction "2_2") (pintype "passive"))
    )
    (net (code "68") (name "Net-(L3-Pad1)") (class "Default")
      (node (ref "L3") (pin "1") (pinfunction "1_1") (pintype "passive"))
      (node (ref "R6") (pin "1") (pinfunction "1_1") (pintype "passive"))
    )
    (net (code "69") (name "Net-(LED1-PadC)") (class "Default")
      (node (ref "LED1") (pin "C") (pinfunction "C_C") (pintype "passive"))
      (node (ref "R15") (pin "2") (pinfunction "2_2") (pintype "passive"))
    )
    (net (code "70") (name "Net-(LED2-PadA)") (class "Default")
      (node (ref "LED2") (pin "A") (pinfunction "A_A") (pintype "passive"))
      (node (ref "R5") (pin "1") (pinfunction "1_1") (pintype "passive"))
    )
    (net (code "71") (name "Net-(RN2A-2)") (class "Default")
      (node (ref "ON") (pin "A") (pinfunction "A_A") (pintype "passive"))
      (node (ref "RN2") (pin "8") (pinfunction "2_8") (pintype "passive"))
    )
    (net (code "72") (name "Net-(RN2B-2)") (class "Default")
      (node (ref "L") (pin "A") (pinfunction "A_A") (pintype "passive"))
      (node (ref "RN2") (pin "7") (pinfunction "2_7") (pintype "passive"))
    )
    (net (code "73") (name "Net-(RN2C-2)") (class "Default")
      (node (ref "RN2") (pin "6") (pinfunction "2_6") (pintype "passive"))
      (node (ref "TX") (pin "A") (pinfunction "A_A") (pintype "passive"))
    )
    (net (code "74") (name "Net-(RN2D-2)") (class "Default")
      (node (ref "RN2") (pin "5") (pinfunction "2_5") (pintype "passive"))
      (node (ref "RX") (pin "A") (pinfunction "A_A") (pintype "passive"))
    )
    (net (code "75") (name "Net-(U$10-3_TIMEPULSE)") (class "Default")
      (node (ref "R5") (pin "2") (pinfunction "2_2") (pintype "passive"))
      (node (ref "U$10") (pin "3") (pinfunction "3_TIMEPULSE_3") (pintype "bidirectional"))
    )
    (net (code "76") (name "Net-(U$10-8_RESET_N)") (class "Default")
      (node (ref "R6") (pin "2") (pinfunction "2_2") (pintype "passive"))
      (node (ref "U$10") (pin "8") (pinfunction "8_RESET_N_8") (pintype "bidirectional"))
      (node (ref "U$10") (pin "9") (pinfunction "9_VCC_RF_9") (pintype "bidirectional"))
    )
    (net (code "77") (name "Net-(U$10-11_RF_IN)") (class "Default")
      (node (ref "L3") (pin "2") (pinfunction "2_2") (pintype "passive"))
      (node (ref "U$10") (pin "11") (pinfunction "11_RF_IN_11") (pintype "bidirectional"))
      (node (ref "X3") (pin "3") (pinfunction "SIGNAL_3") (pintype "passive"))
    )
    (net (code "78") (name "Net-(U4-PWRKEY)") (class "Default")
      (node (ref "D7") (pin "A") (pinfunction "A_A") (pintype "passive"))
      (node (ref "U4") (pin "48") (pinfunction "PWRKEY_48") (pintype "input"))
    )
    (net (code "79") (name "UGND") (class "Default")
      (node (ref "C7") (pin "2") (pinfunction "2_2") (pintype "passive"))
      (node (ref "J1") (pin "P5") (pinfunction "GND_P5") (pintype "passive"))
      (node (ref "L2") (pin "1") (pinfunction "1_1") (pintype "passive"))
      (node (ref "R3") (pin "2") (pinfunction "2_2") (pintype "passive"))
      (node (ref "U2") (pin "5") (pinfunction "UGND_5") (pintype "power_in"))
    )
    (net (code "80") (name "VUSB") (class "Default")
      (node (ref "C8") (pin "+") (pinfunction "+_+") (pintype "passive"))
      (node (ref "C9") (pin "2") (pinfunction "2_2") (pintype "passive"))
      (node (ref "F1") (pin "1") (pinfunction "1_1") (pintype "passive"))
      (node (ref "R4") (pin "2") (pinfunction "2_2") (pintype "passive"))
      (node (ref "T1") (pin "1") (pinfunction "D_1") (pintype "passive"))
      (node (ref "U2") (pin "7") (pinfunction "VBUS_7") (pintype "input"))
    )
    (net (code "81") (name "unconnected-(D5-C5-Pad6)") (class "Default")
      (node (ref "D5") (pin "6") (pinfunction "C5_6") (pintype "passive"))
    )
    (net (code "82") (name "unconnected-(U$10-1_SAFEBOOT_N-Pad1)") (class "Default")
      (node (ref "U$10") (pin "1") (pinfunction "1_SAFEBOOT_N_1") (pintype "bidirectional"))
    )
    (net (code "83") (name "unconnected-(U$10-2_D_SEL-Pad2)") (class "Default")
      (node (ref "U$10") (pin "2") (pinfunction "2_D_SEL_2") (pintype "bidirectional"))
    )
    (net (code "84") (name "unconnected-(U$10-4_EXTINT-Pad4)") (class "Default")
      (node (ref "U$10") (pin "4") (pinfunction "4_EXTINT_4") (pintype "bidirectional"))
    )
    (net (code "85") (name "unconnected-(U$10-5_USB_DM-Pad5)") (class "Default")
      (node (ref "U$10") (pin "5") (pinfunction "5_USB_DM_5") (pintype "bidirectional"))
    )
    (net (code "86") (name "unconnected-(U$10-6_USB_DP-Pad6)") (class "Default")
      (node (ref "U$10") (pin "6") (pinfunction "6_USB_DP_6") (pintype "bidirectional"))
    )
    (net (code "87") (name "unconnected-(U$10-14_LNA_EN{slash}RESERVED-Pad14)") (class "Default")
      (node (ref "U$10") (pin "14") (pinfunction "14_LNA_EN/RESERVED_14") (pintype "bidirectional"))
    )
    (net (code "88") (name "unconnected-(U$10-15_RESERVED-Pad15)") (class "Default")
      (node (ref "U$10") (pin "15") (pinfunction "15_RESERVED_15") (pintype "bidirectional"))
    )
    (net (code "89") (name "unconnected-(U$10-16_RESERVED-Pad16)") (class "Default")
      (node (ref "U$10") (pin "16") (pinfunction "16_RESERVED_16") (pintype "bidirectional"))
    )
    (net (code "90") (name "unconnected-(U$10-17_RESERVED-Pad17)") (class "Default")
      (node (ref "U$10") (pin "17") (pinfunction "17_RESERVED_17") (pintype "bidirectional"))
    )
    (net (code "91") (name "unconnected-(U3-NC{slash}FB-Pad4)") (class "Default")
      (node (ref "U3") (pin "4") (pinfunction "NC/FB_4") (pintype "passive"))
    )
    (net (code "92") (name "unconnected-(U4-ADC-Pad50)") (class "Default")
      (node (ref "U4") (pin "50") (pinfunction "ADC_50") (pintype "input"))
    )
    (net (code "93") (name "unconnected-(U4-BPI_BUS1-Pad5)") (class "Default")
      (node (ref "U4") (pin "5") (pinfunction "BPI_BUS1_5") (pintype "output"))
    )
    (net (code "94") (name "unconnected-(U4-COL0-Pad20)") (class "Default")
      (node (ref "U4") (pin "20") (pinfunction "COL0_20") (pintype "bidirectional"))
    )
    (net (code "95") (name "unconnected-(U4-COL1-Pad25)") (class "Default")
      (node (ref "U4") (pin "25") (pinfunction "COL1_25") (pintype "bidirectional"))
    )
    (net (code "96") (name "unconnected-(U4-COL2-Pad22)") (class "Default")
      (node (ref "U4") (pin "22") (pinfunction "COL2_22") (pintype "bidirectional"))
    )
    (net (code "97") (name "unconnected-(U4-COL3-Pad21)") (class "Default")
      (node (ref "U4") (pin "21") (pinfunction "COL3_21") (pintype "bidirectional"))
    )
    (net (code "98") (name "unconnected-(U4-COL4-Pad24)") (class "Default")
      (node (ref "U4") (pin "24") (pinfunction "COL4_24") (pintype "bidirectional"))
    )
    (net (code "99") (name "unconnected-(U4-FM_ANT_N-Pad57)") (class "Default")
      (node (ref "U4") (pin "57") (pinfunction "FM_ANT_N_57") (pintype "bidirectional"))
    )
    (net (code "100") (name "unconnected-(U4-FM_ANT_P-Pad17)") (class "Default")
      (node (ref "U4") (pin "17") (pinfunction "FM_ANT_P_17") (pintype "bidirectional"))
    )
    (net (code "101") (name "unconnected-(U4-GPIO1-Pad3)") (class "Default")
      (node (ref "U4") (pin "3") (pinfunction "GPIO1_3") (pintype "bidirectional"))
    )
    (net (code "102") (name "unconnected-(U4-GPIO2-Pad27)") (class "Default")
      (node (ref "U4") (pin "27") (pinfunction "GPIO2_27") (pintype "bidirectional"))
    )
    (net (code "103") (name "unconnected-(U4-GPIO3-Pad28)") (class "Default")
      (node (ref "U4") (pin "28") (pinfunction "GPIO3_28") (pintype "bidirectional"))
    )
    (net (code "104") (name "unconnected-(U4-ISINK0-Pad47)") (class "Default")
      (node (ref "U4") (pin "47") (pinfunction "ISINK0_47") (pintype "input"))
    )
    (net (code "105") (name "unconnected-(U4-ISINK1-Pad46)") (class "Default")
      (node (ref "U4") (pin "46") (pinfunction "ISINK1_46") (pintype "input"))
    )
    (net (code "106") (name "unconnected-(U4-MIC1N-Pad12)") (class "Default")
      (node (ref "U4") (pin "12") (pinfunction "MIC1N_12") (pintype "input"))
    )
    (net (code "107") (name "unconnected-(U4-MIC1P-Pad52)") (class "Default")
      (node (ref "U4") (pin "52") (pinfunction "MIC1P_52") (pintype "input"))
    )
    (net (code "108") (name "unconnected-(U4-MIC2N-Pad10)") (class "Default")
      (node (ref "U4") (pin "10") (pinfunction "MIC2N_10") (pintype "input"))
    )
    (net (code "109") (name "unconnected-(U4-MIC2P-Pad9)") (class "Default")
      (node (ref "U4") (pin "9") (pinfunction "MIC2P_9") (pintype "input"))
    )
    (net (code "110") (name "unconnected-(U4-NC-Pad36)") (class "Default")
      (node (ref "U4") (pin "36") (pinfunction "NC_36") (pintype "no_connect"))
    )
    (net (code "111") (name "unconnected-(U4-PCMCLK-Pad29)") (class "Default")
      (node (ref "U4") (pin "29") (pinfunction "PCMCLK_29") (pintype "output"))
    )
    (net (code "112") (name "unconnected-(U4-PCMIN-Pad66)") (class "Default")
      (node (ref "U4") (pin "66") (pinfunction "PCMIN_66") (pintype "input"))
    )
    (net (code "113") (name "unconnected-(U4-PCMOUT-Pad30)") (class "Default")
      (node (ref "U4") (pin "30") (pinfunction "PCMOUT_30") (pintype "output"))
    )
    (net (code "114") (name "unconnected-(U4-PCMSYNC-Pad65)") (class "Default")
      (node (ref "U4") (pin "65") (pinfunction "PCMSYNC_65") (pintype "output"))
    )
    (net (code "115") (name "unconnected-(U4-PWM-Pad26)") (class "Default")
      (node (ref "U4") (pin "26") (pinfunction "PWM_26") (pintype "output"))
    )
    (net (code "116") (name "unconnected-(U4-ROW0-Pad62)") (class "Default")
      (node (ref "U4") (pin "62") (pinfunction "ROW0_62") (pintype "bidirectional"))
    )
    (net (code "117") (name "unconnected-(U4-ROW1-Pad60)") (class "Default")
      (node (ref "U4") (pin "60") (pinfunction "ROW1_60") (pintype "bidirectional"))
    )
    (net (code "118") (name "unconnected-(U4-ROW2-Pad61)") (class "Default")
      (node (ref "U4") (pin "61") (pinfunction "ROW2_61") (pintype "bidirectional"))
    )
    (net (code "119") (name "unconnected-(U4-ROW3-Pad23)") (class "Default")
      (node (ref "U4") (pin "23") (pinfunction "ROW3_23") (pintype "bidirectional"))
    )
    (net (code "120") (name "unconnected-(U4-ROW4-Pad63)") (class "Default")
      (node (ref "U4") (pin "63") (pinfunction "ROW4_63") (pintype "bidirectional"))
    )
    (net (code "121") (name "unconnected-(U4-SCL-Pad74)") (class "Default")
      (node (ref "U4") (pin "74") (pinfunction "SCL_74") (pintype "bidirectional"))
    )
    (net (code "122") (name "unconnected-(U4-SDA-Pad75)") (class "Default")
      (node (ref "U4") (pin "75") (pinfunction "SDA_75") (pintype "bidirectional"))
    )
    (net (code "123") (name "unconnected-(U4-SIMPRE-Pad54)") (class "Default")
      (node (ref "U4") (pin "54") (pinfunction "SIMPRE_54") (pintype "input"))
    )
    (net (code "124") (name "unconnected-(U4-SPK1N-Pad13)") (class "Default")
      (node (ref "U4") (pin "13") (pinfunction "SPK1N_13") (pintype "output"))
    )
    (net (code "125") (name "unconnected-(U4-SPK1P-Pad53)") (class "Default")
      (node (ref "U4") (pin "53") (pinfunction "SPK1P_53") (pintype "output"))
    )
    (net (code "126") (name "unconnected-(U4-SPK2N-Pad11)") (class "Default")
      (node (ref "U4") (pin "11") (pinfunction "SPK2N_11") (pintype "output"))
    )
    (net (code "127") (name "unconnected-(U4-SPK2P{slash}8Ω-Pad51)") (class "Default")
      (node (ref "U4") (pin "51") (pinfunction "SPK2P/8Ω_51") (pintype "output"))
    )
    (net (code "128") (name "unconnected-(U4-UART_CTS-Pad34)") (class "Default")
      (node (ref "U4") (pin "34") (pinfunction "UART_CTS_34") (pintype "output"))
    )
    (net (code "129") (name "unconnected-(U4-UART_DCD-Pad70)") (class "Default")
      (node (ref "U4") (pin "70") (pinfunction "UART_DCD_70") (pintype "input"))
    )
    (net (code "130") (name "unconnected-(U4-UART_DTR-Pad69)") (class "Default")
      (node (ref "U4") (pin "69") (pinfunction "UART_DTR_69") (pintype "input"))
    )
    (net (code "131") (name "unconnected-(U4-UART_RTS-Pad33)") (class "Default")
      (node (ref "U4") (pin "33") (pinfunction "UART_RTS_33") (pintype "input"))
    )
    (net (code "132") (name "unconnected-(U4-USB_DM-Pad19)") (class "Default")
      (node (ref "U4") (pin "19") (pinfunction "USB_DM_19") (pintype "bidirectional"))
    )
    (net (code "133") (name "unconnected-(U4-USB_DP-Pad59)") (class "Default")
      (node (ref "U4") (pin "59") (pinfunction "USB_DP_59") (pintype "bidirectional"))
    )
    (net (code "134") (name "unconnected-(U6-BYP-Pad4)") (class "Default")
      (node (ref "U6") (pin "4") (pinfunction "BYP_4") (pintype "passive"))
    )
    (net (code "135") (name "unconnected-(X2-PadVPP)") (class "Default")
      (node (ref "X2") (pin "VPP") (pinfunction "VPP_VPP") (pintype "passive"))
    )
  )
)
